# 05_-_Probe_Line_IO_Expanders.net
KiCad netlist of a schematic drawn in Altium Designer
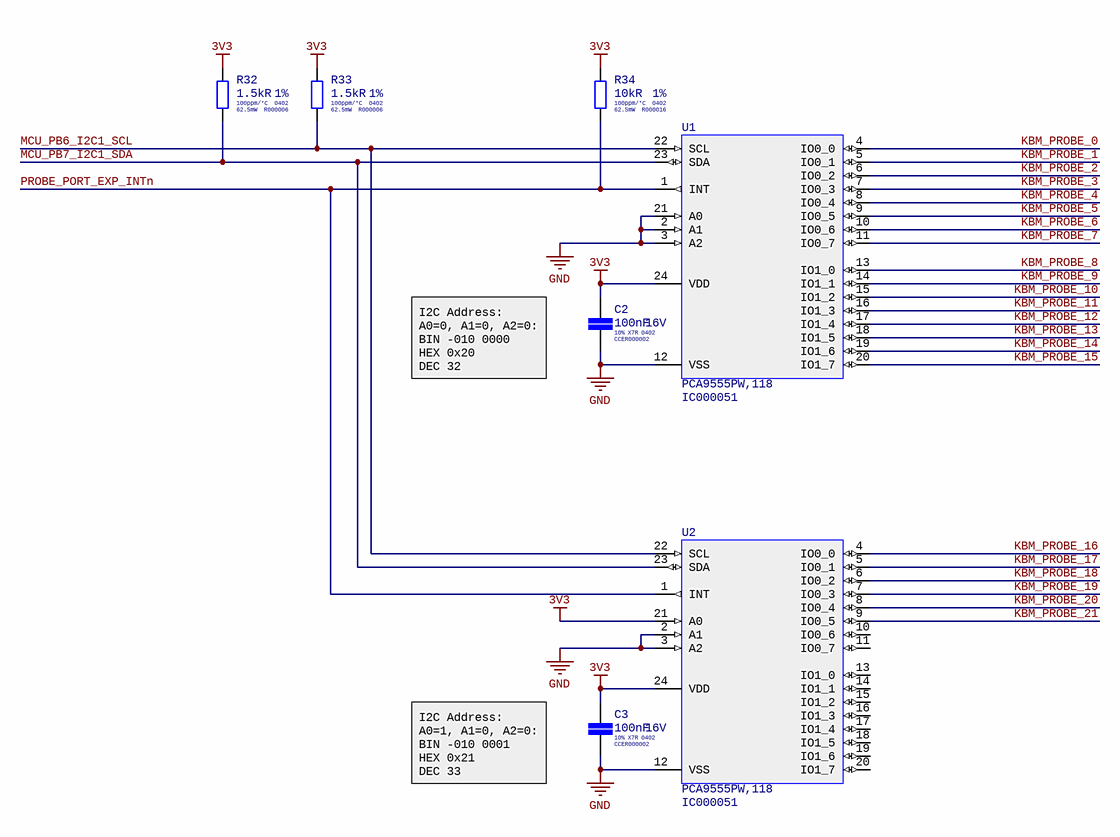
[diagram p0: [05] - Probe Line IO Expanders.SchDoc]

(export (version "E")
  (design (tool "Eeschema 10.0.6"))
  (components
    (comp (ref "C2")
      (value "100nF 16V")
      (footprint "CAP-SMD-0402-0.55MM-IPC-MED")
      (description "CAP CER 100N 16V X7R 10% SMD 0402 125C SAMSUNG")
      (fields
        (field (name "VOLTAGE") "16V")
        (field (name "TOLERANCE") "10%")
        (field (name "INTERNAL PART NUMBER") "CCER000002")
        (field (name "VOLTAGE RATING (DC)") "16V")
        (field (name "DIELECTRIC") "X7R")
        (field (name "CASE/PACKAGE") "0402")
        (field (name "CAPACITANCE") "100nF")
      )
      (libsource (lib "Altium_Lib_Standard") (part "CL05B104KO5NNNC"))
    )
    (comp (ref "C3")
      (value "100nF 16V")
      (footprint "CAP-SMD-0402-0.55MM-IPC-MED")
      (description "CAP CER 100N 16V X7R 10% SMD 0402 125C SAMSUNG")
      (fields
        (field (name "VOLTAGE") "16V")
        (field (name "TOLERANCE") "10%")
        (field (name "INTERNAL PART NUMBER") "CCER000002")
        (field (name "VOLTAGE RATING (DC)") "16V")
        (field (name "DIELECTRIC") "X7R")
        (field (name "CASE/PACKAGE") "0402")
        (field (name "CAPACITANCE") "100nF")
      )
      (libsource (lib "Altium_Lib_Standard") (part "CL05B104KO5NNNC"))
    )
    (comp (ref "R32")
      (value "1.5kR 1%")
      (footprint "RES-SMD-0402-0.4MM-IPC-MED")
      (description "RES 1K5 1% 1/16W SMD 0402 YAEGO")
      (fields
        (field (name "MANUFACTURER") "Yageo")
        (field (name "MANUFACTURER PART NUMBER") "RC0402FR-071K5L")
        (field (name "TEMPERATURE COEFFICIENT") "100ppm/°C")
        (field (name "TOLERANCE") "1%")
        (field (name "RESISTANCE") "1.5kR")
        (field (name "MAX POWER DISSIPATION") "62.5mW")
        (field (name "CASE/PACKAGE") "0402")
        (field (name "INTERNAL PART NUMBER") "R000006")
      )
      (libsource (lib "Altium_Lib_Standard") (part "RC0402FR-071K5L"))
    )
    (comp (ref "R33")
      (value "1.5kR 1%")
      (footprint "RES-SMD-0402-0.4MM-IPC-MED")
      (description "RES 1K5 1% 1/16W SMD 0402 YAEGO")
      (fields
        (field (name "MANUFACTURER") "Yageo")
        (field (name "MANUFACTURER PART NUMBER") "RC0402FR-071K5L")
        (field (name "TEMPERATURE COEFFICIENT") "100ppm/°C")
        (field (name "TOLERANCE") "1%")
        (field (name "RESISTANCE") "1.5kR")
        (field (name "MAX POWER DISSIPATION") "62.5mW")
        (field (name "CASE/PACKAGE") "0402")
        (field (name "INTERNAL PART NUMBER") "R000006")
      )
      (libsource (lib "Altium_Lib_Standard") (part "RC0402FR-071K5L"))
    )
    (comp (ref "R34")
      (value "10kR 1%")
      (footprint "RES-SMD-0402-0.4MM-IPC-MED")
      (description "RES 10K 1% 1/16W SMD 0402 YAEGO")
      (fields
        (field (name "MANUFACTURER") "Yageo")
        (field (name "MANUFACTURER PART NUMBER") "RC0402FR-0710KL")
        (field (name "TOLERANCE") "1%")
        (field (name "TEMPERATURE COEFFICIENT") "100ppm/°C")
        (field (name "RESISTANCE") "10kR")
        (field (name "POWER RATING") "62.5mW")
        (field (name "CASE CODE (IMPERIAL)") "0402")
        (field (name "INTERNAL PART NUMBER") "R000016")
      )
      (libsource (lib "Altium_Lib_Standard") (part "RC0402FR-0710KL"))
    )
    (comp (ref "U1")
      (value "PCA9555PW,118")
      (footprint "TSSOP-24-H1.1MM-P0.65MM-NXP")
      (description "IC I/O EXPANDER I2C 16B 24TSSOP")
      (fields
        (field (name "MANUFACTURER") "NXP Semiconductors")
        (field (name "INTERNAL PART NUMBER") "IC000051")
      )
      (libsource (lib "Altium_Lib_Standard") (part "PCA9555PW,118"))
    )
    (comp (ref "U2")
      (value "PCA9555PW,118")
      (footprint "TSSOP-24-H1.1MM-P0.65MM-NXP")
      (description "IC I/O EXPANDER I2C 16B 24TSSOP")
      (fields
        (field (name "MANUFACTURER") "NXP Semiconductors")
        (field (name "INTERNAL PART NUMBER") "IC000051")
      )
      (libsource (lib "Altium_Lib_Standard") (part "PCA9555PW,118"))
    )
  )
  (nets
    (net (code "1") (name "/KBM_PROBE_0") (class "Default")
      (node (ref "U1") (pin "4") (pinfunction "IO0_0_4") (pintype "bidirectional"))
    )
    (net (code "2") (name "/KBM_PROBE_1") (class "Default")
      (node (ref "U1") (pin "5") (pinfunction "IO0_1_5") (pintype "bidirectional"))
    )
    (net (code "3") (name "/KBM_PROBE_2") (class "Default")
      (node (ref "U1") (pin "6") (pinfunction "IO0_2_6") (pintype "bidirectional"))
    )
    (net (code "4") (name "/KBM_PROBE_3") (class "Default")
      (node (ref "U1") (pin "7") (pinfunction "IO0_3_7") (pintype "bidirectional"))
    )
    (net (code "5") (name "/KBM_PROBE_4") (class "Default")
      (node (ref "U1") (pin "8") (pinfunction "IO0_4_8") (pintype "bidirectional"))
    )
    (net (code "6") (name "/KBM_PROBE_5") (class "Default")
      (node (ref "U1") (pin "9") (pinfunction "IO0_5_9") (pintype "bidirectional"))
    )
    (net (code "7") (name "/KBM_PROBE_6") (class "Default")
      (node (ref "U1") (pin "10") (pinfunction "IO0_6_10") (pintype "bidirectional"))
    )
    (net (code "8") (name "/KBM_PROBE_7") (class "Default")
      (node (ref "U1") (pin "11") (pinfunction "IO0_7_11") (pintype "bidirectional"))
    )
    (net (code "9") (name "/KBM_PROBE_8") (class "Default")
      (node (ref "U1") (pin "13") (pinfunction "IO1_0_13") (pintype "bidirectional"))
    )
    (net (code "10") (name "/KBM_PROBE_9") (class "Default")
      (node (ref "U1") (pin "14") (pinfunction "IO1_1_14") (pintype "bidirectional"))
    )
    (net (code "11") (name "/KBM_PROBE_10") (class "Default")
      (node (ref "U1") (pin "15") (pinfunction "IO1_2_15") (pintype "bidirectional"))
    )
    (net (code "12") (name "/KBM_PROBE_11") (class "Default")
      (node (ref "U1") (pin "16") (pinfunction "IO1_3_16") (pintype "bidirectional"))
    )
    (net (code "13") (name "/KBM_PROBE_12") (class "Default")
      (node (ref "U1") (pin "17") (pinfunction "IO1_4_17") (pintype "bidirectional"))
    )
    (net (code "14") (name "/KBM_PROBE_13") (class "Default")
      (node (ref "U1") (pin "18") (pinfunction "IO1_5_18") (pintype "bidirectional"))
    )
    (net (code "15") (name "/KBM_PROBE_14") (class "Default")
      (node (ref "U1") (pin "19") (pinfunction "IO1_6_19") (pintype "bidirectional"))
    )
    (net (code "16") (name "/KBM_PROBE_15") (class "Default")
      (node (ref "U1") (pin "20") (pinfunction "IO1_7_20") (pintype "bidirectional"))
    )
    (net (code "17") (name "/KBM_PROBE_16") (class "Default")
      (node (ref "U2") (pin "4") (pinfunction "IO0_0_4") (pintype "bidirectional"))
    )
    (net (code "18") (name "/KBM_PROBE_17") (class "Default")
      (node (ref "U2") (pin "5") (pinfunction "IO0_1_5") (pintype "bidirectional"))
    )
    (net (code "19") (name "/KBM_PROBE_18") (class "Default")
      (node (ref "U2") (pin "6") (pinfunction "IO0_2_6") (pintype "bidirectional"))
    )
    (net (code "20") (name "/KBM_PROBE_19") (class "Default")
      (node (ref "U2") (pin "7") (pinfunction "IO0_3_7") (pintype "bidirectional"))
    )
    (net (code "21") (name "/KBM_PROBE_20") (class "Default")
      (node (ref "U2") (pin "8") (pinfunction "IO0_4_8") (pintype "bidirectional"))
    )
    (net (code "22") (name "/KBM_PROBE_21") (class "Default")
      (node (ref "U2") (pin "9") (pinfunction "IO0_5_9") (pintype "bidirectional"))
    )
    (net (code "23") (name "/MCU_PB6_I2C1_SCL") (class "Default")
      (node (ref "R33") (pin "2") (pinfunction "2_2") (pintype "passive"))
      (node (ref "U1") (pin "22") (pinfunction "SCL_22") (pintype "input"))
      (node (ref "U2") (pin "22") (pinfunction "SCL_22") (pintype "input"))
    )
    (net (code "24") (name "/MCU_PB7_I2C1_SDA") (class "Default")
      (node (ref "R32") (pin "2") (pinfunction "2_2") (pintype "passive"))
      (node (ref "U1") (pin "23") (pinfunction "SDA_23") (pintype "bidirectional"))
      (node (ref "U2") (pin "23") (pinfunction "SDA_23") (pintype "bidirectional"))
    )
    (net (code "25") (name "/PROBE_PORT_EXP_INTn") (class "Default")
      (node (ref "R34") (pin "2") (pinfunction "2_2") (pintype "passive"))
      (node (ref "U1") (pin "1") (pinfunction "INT_1") (pintype "output"))
      (node (ref "U2") (pin "1") (pinfunction "INT_1") (pintype "output"))
    )
    (net (code "26") (name "3V3") (class "Default")
      (node (ref "C2") (pin "1") (pinfunction "1_1") (pintype "passive"))
      (node (ref "C3") (pin "1") (pinfunction "1_1") (pintype "passive"))
      (node (ref "R32") (pin "1") (pinfunction "1_1") (pintype "passive"))
      (node (ref "R33") (pin "1") (pinfunction "1_1") (pintype "passive"))
      (node (ref "R34") (pin "1") (pinfunction "1_1") (pintype "passive"))
      (node (ref "U1") (pin "24") (pinfunction "VDD_24") (pintype "power_in"))
      (node (ref "U2") (pin "21") (pinfunction "A0_21") (pintype "input"))
      (node (ref "U2") (pin "24") (pinfunction "VDD_24") (pintype "power_in"))
    )
    (net (code "27") (name "GND") (class "Default")
      (node (ref "C2") (pin "2") (pinfunction "2_2") (pintype "passive"))
      (node (ref "C3") (pin "2") (pinfunction "2_2") (pintype "passive"))
      (node (ref "U1") (pin "12") (pinfunction "VSS_12") (pintype "power_in"))
      (node (ref "U1") (pin "2") (pinfunction "A1_2") (pintype "input"))
      (node (ref "U1") (pin "21") (pinfunction "A0_21") (pintype "input"))
      (node (ref "U1") (pin "3") (pinfunction "A2_3") (pintype "input"))
      (node (ref "U2") (pin "12") (pinfunction "VSS_12") (pintype "power_in"))
      (node (ref "U2") (pin "2") (pinfunction "A1_2") (pintype "input"))
      (node (ref "U2") (pin "3") (pinfunction "A2_3") (pintype "input"))
    )
    (net (code "28") (name "unconnected-(U2-IO0_6-Pad10)") (class "Default")
      (node (ref "U2") (pin "10") (pinfunction "IO0_6_10") (pintype "bidirectional"))
    )
    (net (code "29") (name "unconnected-(U2-IO0_7-Pad11)") (class "Default")
      (node (ref "U2") (pin "11") (pinfunction "IO0_7_11") (pintype "bidirectional"))
    )
    (net (code "30") (name "unconnected-(U2-IO1_0-Pad13)") (class "Default")
      (node (ref "U2") (pin "13") (pinfunction "IO1_0_13") (pintype "bidirectional"))
    )
    (net (code "31") (name "unconnected-(U2-IO1_1-Pad14)") (class "Default")
      (node (ref "U2") (pin "14") (pinfunction "IO1_1_14") (pintype "bidirectional"))
    )
    (net (code "32") (name "unconnected-(U2-IO1_2-Pad15)") (class "Default")
      (node (ref "U2") (pin "15") (pinfunction "IO1_2_15") (pintype "bidirectional"))
    )
    (net (code "33") (name "unconnected-(U2-IO1_3-Pad16)") (class "Default")
      (node (ref "U2") (pin "16") (pinfunction "IO1_3_16") (pintype "bidirectional"))
    )
    (net (code "34") (name "unconnected-(U2-IO1_4-Pad17)") (class "Default")
      (node (ref "U2") (pin "17") (pinfunction "IO1_4_17") (pintype "bidirectional"))
    )
    (net (code "35") (name "unconnected-(U2-IO1_5-Pad18)") (class "Default")
      (node (ref "U2") (pin "18") (pinfunction "IO1_5_18") (pintype "bidirectional"))
    )
    (net (code "36") (name "unconnected-(U2-IO1_6-Pad19)") (class "Default")
      (node (ref "U2") (pin "19") (pinfunction "IO1_6_19") (pintype "bidirectional"))
    )
    (net (code "37") (name "unconnected-(U2-IO1_7-Pad20)") (class "Default")
      (node (ref "U2") (pin "20") (pinfunction "IO1_7_20") (pintype "bidirectional"))
    )
  )
)
